# design.net
KiCad netlist of a schematic drawn in Altium Designer
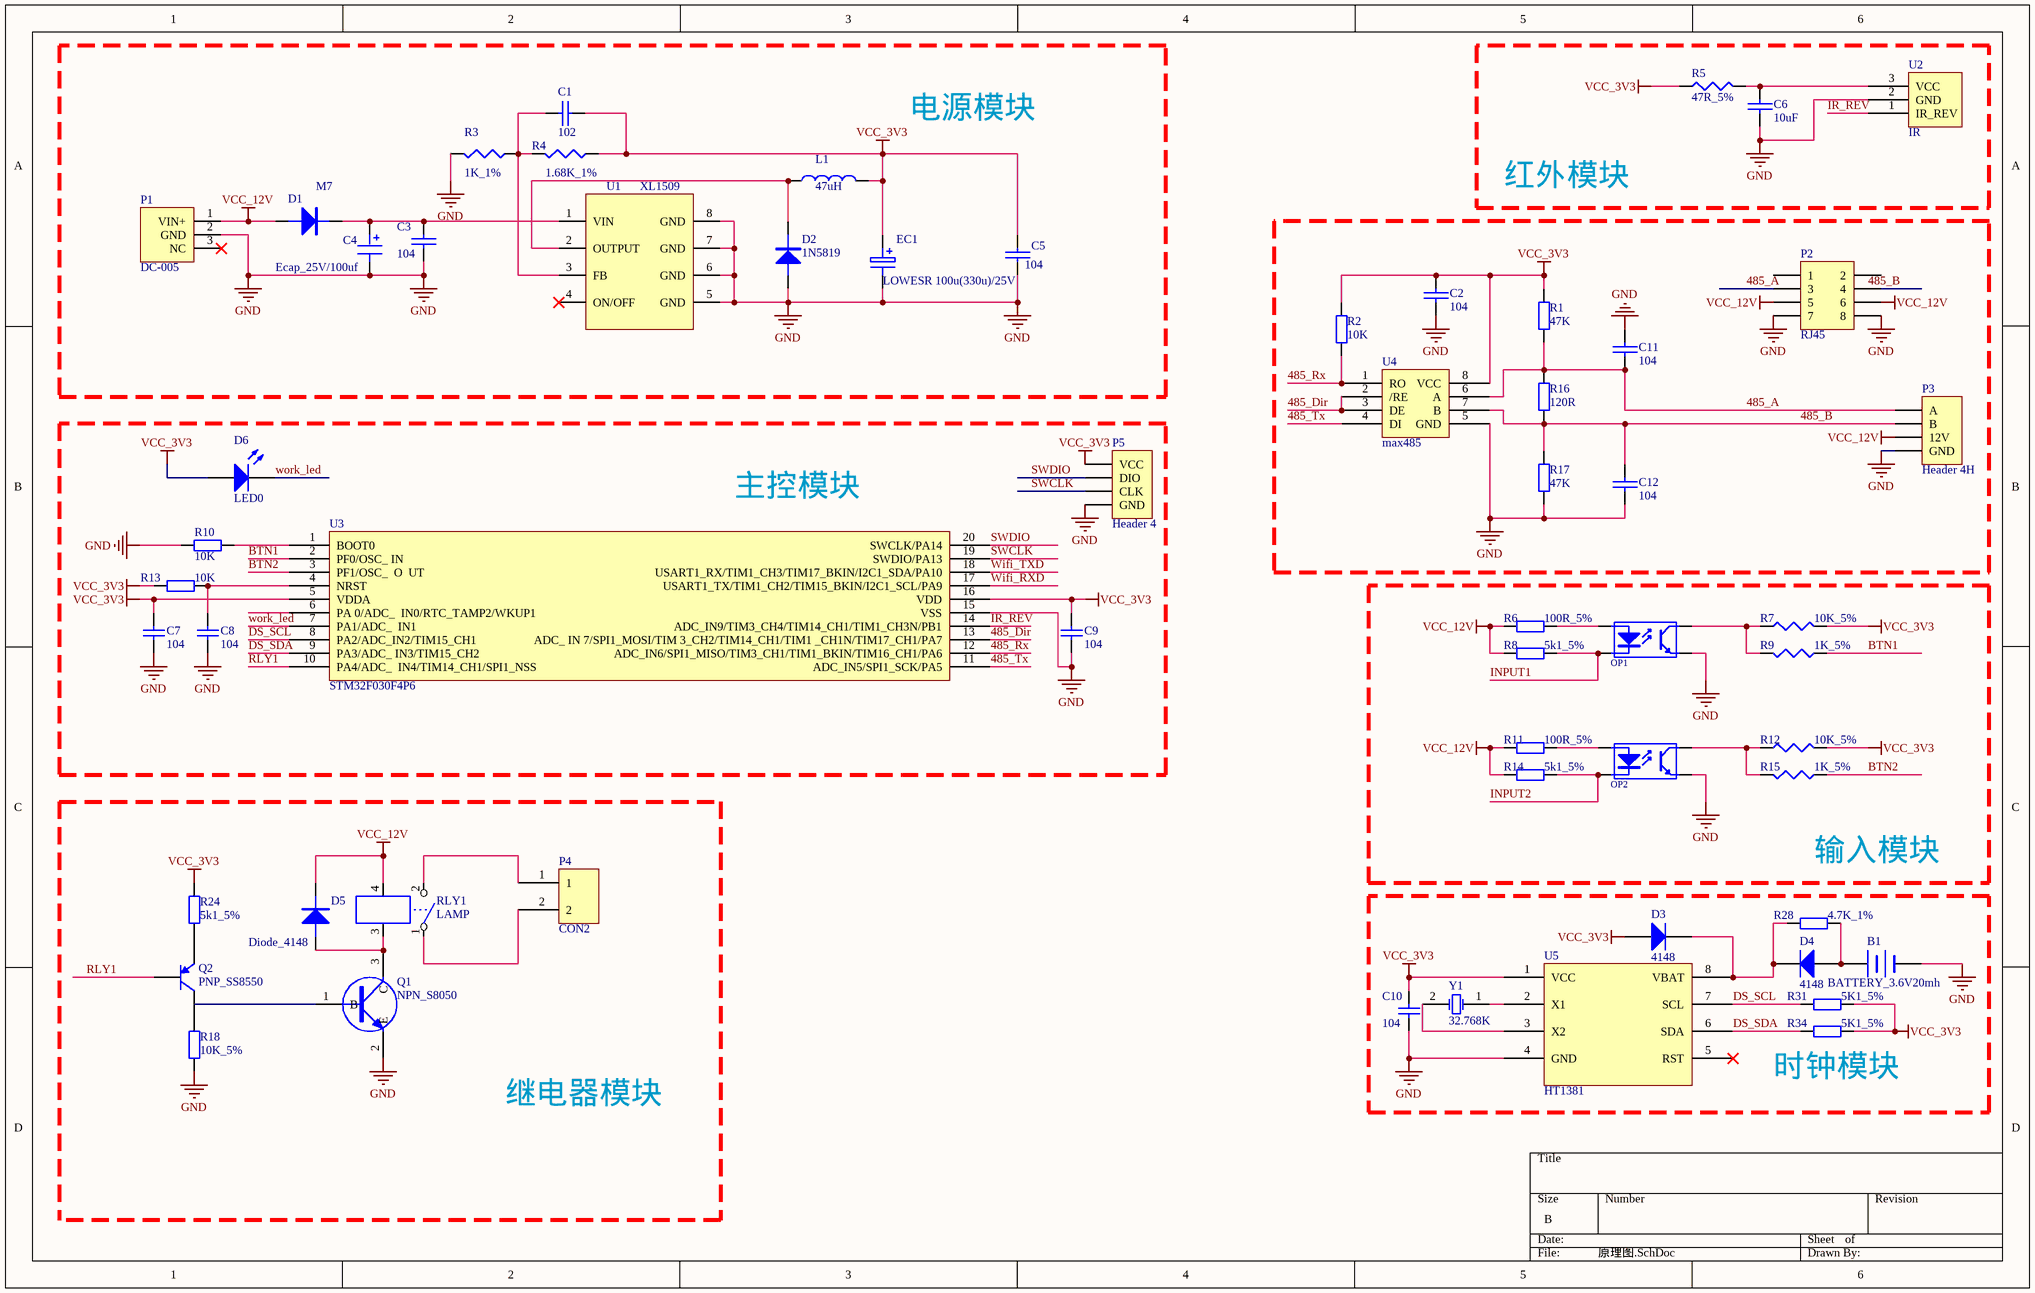
[diagram p0: 原理图.SchDoc]

(export (version "E")
  (design (tool "Eeschema 10.0.6"))
  (components
    (comp (ref "B1")
      (value "BATTERY_3.6V20mh")
      (footprint "NI-MH_20mA+C")
      (description "https://item.taobao.com/item.htm?spm=a1z10.5-c.w4002-471439023.33.YIdXb6&id=524181772992")
      (libsource (lib "NortCele_SchLib") (part "BATTERY_3.6V20mh"))
    )
    (comp (ref "C1") (value "102") (footprint "0603_CAP_SMT") (libsource (lib "*") (part "CAP")))
    (comp (ref "C2") (value "104") (footprint "0603_CAP_SMT") (libsource (lib "*") (part "CAP")))
    (comp (ref "C3") (value "104") (footprint "0603_CAP_SMT") (libsource (lib "*") (part "CAP")))
    (comp (ref "C4")
      (value "Ecap_25V/100uf")
      (footprint "SMT_CAP6.3")
      (description "https://item.taobao.com/item.htm?spm=a1z10.5-c.w4002-11020631983.33.qoX6of&id=7423722992")
      (libsource (lib "NortCele_SchLib") (part "Ecap_25V/100uf"))
    )
    (comp (ref "C5") (value "104") (footprint "0603_CAP_SMT") (libsource (lib "*") (part "CAP")))
    (comp (ref "C6") (value "10uF") (footprint "0805_CAP") (libsource (lib "Ruibo") (part "CAP")))
    (comp (ref "C7")
      (value "104")
      (footprint "C0402")
      (description "Capacitor")
      (fields (field (name "PUBLISHER") "Altium Limited"))
      (libsource (lib "Miscellaneous Devices") (part "Cap"))
    )
    (comp (ref "C8")
      (value "104")
      (footprint "C0402")
      (description "Capacitor")
      (fields (field (name "PUBLISHER") "Altium Limited"))
      (libsource (lib "Miscellaneous Devices") (part "Cap"))
    )
    (comp (ref "C9")
      (value "104")
      (footprint "C0402")
      (description "Capacitor")
      (fields (field (name "PUBLISHER") "Altium Limited"))
      (libsource (lib "Miscellaneous Devices") (part "Cap"))
    )
    (comp (ref "C10")
      (value "104")
      (footprint "0603_C")
      (description "https://item.taobao.com/item.htm?spm=a1z09.2.0.0.hNveX1&id=9716419590&_u=7ok62qs2673")
      (libsource (lib "NortCele_SchLib") (part "Cap_%10"))
    )
    (comp (ref "C11") (value "104") (footprint "0603_CAP_SMT") (libsource (lib "*") (part "CAP")))
    (comp (ref "C12") (value "104") (footprint "0603_CAP_SMT") (libsource (lib "*") (part "CAP")))
    (comp (ref "D1") (value "M7") (footprint "IN5819") (libsource (lib "*") (part "DIODE")))
    (comp (ref "D2") (value "1N5819") (footprint "SMD") (libsource (lib "Ruibo") (part "DIODE")))
    (comp (ref "D3")
      (value "4148")
      (footprint "SMAF_S5")
      (description "High Conductance Fast Diode")
      (fields (field (name "PUBLISHER") "Altium Limited"))
      (libsource (lib "Miscellaneous Devices") (part "Diode 1N914"))
    )
    (comp (ref "D4")
      (value "4148")
      (footprint "SMAF_S5")
      (description "High Conductance Fast Diode")
      (fields (field (name "PUBLISHER") "Altium Limited"))
      (libsource (lib "Miscellaneous Devices") (part "Diode 1N914"))
    )
    (comp (ref "D5")
      (value "Diode_4148")
      (footprint "SMD")
      (description "https://item.taobao.com/item.htm?spm=a1z10.3-c.w4002-11020657456.14.qD67rq&id=6126767310")
      (libsource (lib "NortCele_SchLib") (part "Diode_SS14"))
    )
    (comp (ref "D6")
      (value "LED0")
      (footprint "LED-0")
      (description "Typical INFRARED GaAs LED")
      (fields (field (name "PUBLISHER") "Altium Limited"))
      (libsource (lib "Miscellaneous Devices") (part "LED0"))
    )
    (comp (ref "EC1")
      (value "LOWESR 100u(330u)/25V")
      (footprint "SMT_CAP6.3")
      (libsource (lib "*") (part "ELECTRO1"))
    )
    (comp (ref "L1") (value "47uH") (footprint "0630") (libsource (lib "*") (part "INDUCTOR1")))
    (comp (ref "OP1")
      (value "EL817")
      (footprint "E817-SMD")
      (description "https://item.taobao.com/item.htm?spm=a1z10.3-c.w4002-11020657456.9.xiQJya&id=9840822052")
      (libsource (lib "NortCele_SchLib") (part "EL817"))
    )
    (comp (ref "OP2")
      (value "EL817")
      (footprint "E817-SMD")
      (description "https://item.taobao.com/item.htm?spm=a1z10.3-c.w4002-11020657456.9.xiQJya&id=9840822052")
      (libsource (lib "NortCele_SchLib") (part "EL817"))
    )
    (comp (ref "P1")
      (value "DC-005")
      (footprint "DC-5.5-2.1mm")
      (description "https://item.taobao.com/item.htm?spm=a1z10.3-c.w4002-11020657456.12.3OzBHB&id=5709638982")
      (libsource (lib "NortCele_SchLib") (part "DC-005"))
    )
    (comp (ref "P2")
      (value "RJ45")
      (footprint "HDR2X4")
      (description "Header, 4-Pin, Dual row")
      (fields (field (name "PUBLISHER") "Altium Limited"))
      (libsource (lib "Miscellaneous Connectors") (part "Header 4X2"))
    )
    (comp (ref "P3")
      (value "Header 4H")
      (footprint "HDR1X4H")
      (description "Header, 4-Pin, Right Angle")
      (fields (field (name "PUBLISHER") "Altium Limited"))
      (libsource (lib "Miscellaneous Connectors") (part "Header 4H"))
    )
    (comp (ref "P4") (value "CON2") (footprint "HP2PA-5.08") (libsource (lib "door") (part "CON2")))
    (comp (ref "P5")
      (value "Header 4")
      (footprint "HDR1X4")
      (description "Header, 4-Pin")
      (fields (field (name "PUBLISHER") "Altium Limited"))
      (libsource (lib "Miscellaneous Connectors") (part "Header 4"))
    )
    (comp (ref "Q1")
      (value "NPN_S8050")
      (footprint "SOT-23_FR")
      (description "https://item.taobao.com/item.htm?spm=a1z10.3-c.w4002-11020657456.15.ysrU5Y&id=5957247576")
      (libsource (lib "NortCele_SchLib") (part "NPN_S8050"))
    )
    (comp (ref "Q2")
      (value "PNP_SS8550")
      (footprint "TO-92A")
      (description "PNP General Purpose Amplifier")
      (fields (field (name "PUBLISHER") "Altium Limited"))
      (libsource (lib "Miscellaneous Devices") (part "2N3906"))
    )
    (comp (ref "R1")
      (value "47K")
      (footprint "0603_RES_SMT")
      (description "https://item.taobao.com/item.htm?spm=a1z10.3-c.w4002-11020657456.13.233szV&id=14686636311")
      (libsource (lib "NortCele_SchLib") (part "Res_%5"))
    )
    (comp (ref "R2")
      (value "10K")
      (footprint "0603_RES_SMT")
      (description "https://item.taobao.com/item.htm?spm=a1z10.3-c.w4002-11020657456.13.233szV&id=14686636311")
      (libsource (lib "NortCele_SchLib") (part "Res_%5"))
    )
    (comp (ref "R3") (value "1K_1%") (footprint "0603_RES_SMT") (libsource (lib "Ruibo") (part "RES")))
    (comp (ref "R4") (value "1.68K_1%") (footprint "0603_RES_SMT") (libsource (lib "Ruibo") (part "RES")))
    (comp (ref "R5") (value "47R_5%") (footprint "0805_RES") (libsource (lib "Ruibo") (part "RES")))
    (comp (ref "R6")
      (value "100R_5%")
      (footprint "0805_Res")
      (description "https://item.taobao.com/item.htm?spm=a1z10.3-c.w4002-11020657456.13.233szV&id=14686636311")
      (libsource (lib "NortCele_SchLib") (part "Res_5%"))
    )
    (comp (ref "R7") (value "10K_5%") (footprint "0805_RES") (libsource (lib "Ruibo") (part "RES")))
    (comp (ref "R8")
      (value "5k1_5%")
      (footprint "0805_Res")
      (description "https://item.taobao.com/item.htm?spm=a1z10.3-c.w4002-11020657456.13.233szV&id=14686636311")
      (libsource (lib "NortCele_SchLib") (part "Res_5%"))
    )
    (comp (ref "R9") (value "1K_5%") (footprint "0805_RES") (libsource (lib "Ruibo") (part "RES")))
    (comp (ref "R10")
      (value "10K")
      (footprint "R0402")
      (description "Resistor")
      (fields (field (name "PUBLISHER") "Altium Limited"))
      (libsource (lib "Miscellaneous Devices") (part "Res2"))
    )
    (comp (ref "R11")
      (value "100R_5%")
      (footprint "0805_Res")
      (description "https://item.taobao.com/item.htm?spm=a1z10.3-c.w4002-11020657456.13.233szV&id=14686636311")
      (libsource (lib "NortCele_SchLib") (part "Res_5%"))
    )
    (comp (ref "R12") (value "10K_5%") (footprint "0805_RES") (libsource (lib "Ruibo") (part "RES")))
    (comp (ref "R13")
      (value "10K")
      (footprint "R0402")
      (description "Resistor")
      (fields (field (name "PUBLISHER") "Altium Limited"))
      (libsource (lib "Miscellaneous Devices") (part "Res2"))
    )
    (comp (ref "R14")
      (value "5k1_5%")
      (footprint "0805_Res")
      (description "https://item.taobao.com/item.htm?spm=a1z10.3-c.w4002-11020657456.13.233szV&id=14686636311")
      (libsource (lib "NortCele_SchLib") (part "Res_5%"))
    )
    (comp (ref "R15") (value "1K_5%") (footprint "0805_RES") (libsource (lib "Ruibo") (part "RES")))
    (comp (ref "R16")
      (value "120R")
      (footprint "0603_RES_SMT")
      (description "https://item.taobao.com/item.htm?spm=a1z10.3-c.w4002-11020657456.13.233szV&id=14686636311")
      (libsource (lib "NortCele_SchLib") (part "Res_%5"))
    )
    (comp (ref "R17")
      (value "47K")
      (footprint "0603_RES_SMT")
      (description "https://item.taobao.com/item.htm?spm=a1z10.3-c.w4002-11020657456.13.233szV&id=14686636311")
      (libsource (lib "NortCele_SchLib") (part "Res_%5"))
    )
    (comp (ref "R18")
      (value "10K_5%")
      (footprint "R0402")
      (description "Resistor")
      (fields (field (name "PUBLISHER") "Altium Limited"))
      (libsource (lib "") (part "Res2_1"))
    )
    (comp (ref "R24")
      (value "5k1_5%")
      (footprint "R0402")
      (description "Resistor")
      (fields (field (name "PUBLISHER") "Altium Limited"))
      (libsource (lib "") (part "Res2_1"))
    )
    (comp (ref "R28")
      (value "4.7K_1%")
      (footprint "0603_R")
      (description "https://item.taobao.com/item.htm?spm=a1z10.3-c.w4002-11020657456.13.233szV&id=14686636311")
      (libsource (lib "NortCele_SchLib") (part "Res_5%"))
    )
    (comp (ref "R31")
      (value "5K1_5%")
      (footprint "0603_R")
      (description "https://item.taobao.com/item.htm?spm=a1z10.3-c.w4002-11020657456.13.233szV&id=14686636311")
      (libsource (lib "NortCele_SchLib") (part "Res_5%"))
    )
    (comp (ref "R34")
      (value "5K1_5%")
      (footprint "0603_R")
      (description "https://item.taobao.com/item.htm?spm=a1z10.3-c.w4002-11020657456.13.233szV&id=14686636311")
      (libsource (lib "") (part "Res_5%_1"))
    )
    (comp (ref "RLY1") (value "LAMP") (footprint "SANYOU_RLY112DM") (libsource (lib "*") (part "RELAY-SPST")))
    (comp (ref "U1") (value "XL1509") (footprint "SOP8") (libsource (lib "*") (part "XL1509")))
    (comp (ref "U2")
      (value "IR")
      (footprint "IR_REV_W3")
      (description "红外接收管")
      (libsource (lib "Ruibo") (part "IR_REV"))
    )
    (comp (ref "U3") (value "STM32F030F4P6") (libsource (lib "Schlib1") (part "STM32F030F4P6")))
    (comp (ref "U4") (value "max485") (footprint "SOP8") (libsource (lib "door") (part "max485")))
    (comp (ref "U5") (value "HT1381") (footprint "SOP-8_150mil") (libsource (lib "Schlib1") (part "DS1302")))
    (comp (ref "Y1")
      (value "32.768K")
      (footprint "SMD-3215_2P FC - 135")
      (description "Crystal Oscillator")
      (libsource (lib "Miscellaneous Devices") (part "XTAL"))
    )
  )
  (nets
    (net (code "1") (name "/485_A") (class "Default")
      (node (ref "C11") (pin "1") (pintype "passive"))
      (node (ref "P2") (pin "3") (pinfunction "3_3") (pintype "passive"))
      (node (ref "P3") (pin "1") (pinfunction "A_1") (pintype "passive"))
      (node (ref "R1") (pin "1") (pinfunction "1_1") (pintype "passive"))
      (node (ref "R16") (pin "2") (pinfunction "2_2") (pintype "passive"))
      (node (ref "U4") (pin "6") (pinfunction "A_6") (pintype "passive"))
    )
    (net (code "2") (name "/485_B") (class "Default")
      (node (ref "C12") (pin "2") (pintype "passive"))
      (node (ref "P3") (pin "2") (pinfunction "B_2") (pintype "passive"))
      (node (ref "R16") (pin "1") (pinfunction "1_1") (pintype "passive"))
      (node (ref "R17") (pin "2") (pinfunction "2_2") (pintype "passive"))
      (node (ref "U4") (pin "7") (pinfunction "B_7") (pintype "passive"))
    )
    (net (code "3") (name "/485_Dir") (class "Default")
      (node (ref "U3") (pin "13") (pinfunction "ADC__IN_7/SPI1_MOSI/TIM_3_CH2/TIM14_CH1/TIM1__CH1N/TIM17_CH1/PA7_13") (pintype "passive"))
      (node (ref "U4") (pin "2") (pinfunction "/RE_2") (pintype "passive"))
      (node (ref "U4") (pin "3") (pinfunction "DE_3") (pintype "passive"))
    )
    (net (code "4") (name "/485_Rx") (class "Default")
      (node (ref "R2") (pin "1") (pinfunction "1_1") (pintype "passive"))
      (node (ref "U3") (pin "12") (pinfunction "ADC_IN6/SPI1_MISO/TIM3_CH1/TIM1_BKIN/TIM16_CH1/PA6_12") (pintype "passive"))
      (node (ref "U4") (pin "1") (pinfunction "RO_1") (pintype "passive"))
    )
    (net (code "5") (name "/485_Tx") (class "Default")
      (node (ref "U3") (pin "11") (pinfunction "ADC_IN5/SPI1_SCK/PA5_11") (pintype "passive"))
      (node (ref "U4") (pin "4") (pinfunction "DI_4") (pintype "passive"))
    )
    (net (code "6") (name "/BTN1") (class "Default")
      (node (ref "R9") (pin "1") (pintype "passive"))
      (node (ref "U3") (pin "2") (pinfunction "PF0/OSC__IN_2") (pintype "passive"))
    )
    (net (code "7") (name "/BTN2") (class "Default")
      (node (ref "R15") (pin "1") (pintype "passive"))
      (node (ref "U3") (pin "3") (pinfunction "PF1/OSC___O__UT_3") (pintype "passive"))
    )
    (net (code "8") (name "/DS_SCL") (class "Default")
      (node (ref "R31") (pin "2") (pinfunction "2_2") (pintype "passive"))
      (node (ref "U3") (pin "8") (pinfunction "PA2/ADC_IN2/TIM15_CH1_8") (pintype "passive"))
      (node (ref "U5") (pin "7") (pinfunction "SCL_7") (pintype "passive"))
    )
    (net (code "9") (name "/DS_SDA") (class "Default")
      (node (ref "R34") (pin "1") (pinfunction "1_1") (pintype "passive"))
      (node (ref "U3") (pin "9") (pinfunction "PA3/ADC__IN3/TIM15_CH2_9") (pintype "passive"))
      (node (ref "U5") (pin "6") (pinfunction "SDA_6") (pintype "passive"))
    )
    (net (code "10") (name "/INPUT1") (class "Default")
      (node (ref "OP1") (pin "2") (pinfunction "K_2") (pintype "passive"))
      (node (ref "R8") (pin "1") (pinfunction "1_1") (pintype "passive"))
    )
    (net (code "11") (name "/INPUT2") (class "Default")
      (node (ref "OP2") (pin "2") (pinfunction "K_2") (pintype "passive"))
      (node (ref "R14") (pin "1") (pinfunction "1_1") (pintype "passive"))
    )
    (net (code "12") (name "/IR_REV") (class "Default")
      (node (ref "U2") (pin "1") (pinfunction "IR_REV_1") (pintype "passive"))
      (node (ref "U3") (pin "14") (pinfunction "ADC_IN9/TIM3_CH4/TIM14_CH1/TIM1_CH3N/PB1_14") (pintype "passive"))
    )
    (net (code "13") (name "/RLY1") (class "Default")
      (node (ref "Q2") (pin "2") (pinfunction "B_2") (pintype "passive"))
      (node (ref "U3") (pin "10") (pinfunction "PA4/ADC___IN4/TIM14_CH1/SPI1_NSS_10") (pintype "passive"))
    )
    (net (code "14") (name "/SWCLK") (class "Default")
      (node (ref "P5") (pin "3") (pinfunction "CLK_3") (pintype "passive"))
      (node (ref "U3") (pin "19") (pinfunction "SWDIO/PA13_19") (pintype "passive"))
    )
    (net (code "15") (name "/SWDIO") (class "Default")
      (node (ref "P5") (pin "2") (pinfunction "DIO_2") (pintype "passive"))
      (node (ref "U3") (pin "20") (pinfunction "SWCLK/PA14_20") (pintype "passive"))
    )
    (net (code "16") (name "/Wifi_RXD") (class "Default")
      (node (ref "U3") (pin "17") (pinfunction "USART1_TX/TIM1_CH2/TIM15_BKIN/I2C1_SCL/PA9_17") (pintype "passive"))
    )
    (net (code "17") (name "/Wifi_TXD") (class "Default")
      (node (ref "U3") (pin "18") (pinfunction "USART1_RX/TIM1_CH3/TIM17_BKIN/I2C1_SDA/PA10_18") (pintype "passive"))
    )
    (net (code "18") (name "/work_led") (class "Default")
      (node (ref "D6") (pin "2") (pinfunction "K_2") (pintype "passive"))
      (node (ref "U3") (pin "7") (pinfunction "PA1/ADC___IN1_7") (pintype "passive"))
    )
    (net (code "19") (name "GND") (class "Default")
      (node (ref "B1") (pin "2") (pinfunction "-_2") (pintype "passive"))
      (node (ref "C10") (pin "1") (pinfunction "1_1") (pintype "passive"))
      (node (ref "C11") (pin "2") (pintype "passive"))
      (node (ref "C12") (pin "1") (pintype "passive"))
      (node (ref "C2") (pin "1") (pintype "passive"))
      (node (ref "C3") (pin "2") (pintype "passive"))
      (node (ref "C4") (pin "2") (pinfunction "2_2") (pintype "passive"))
      (node (ref "C5") (pin "2") (pintype "passive"))
      (node (ref "C6") (pin "2") (pintype "passive"))
      (node (ref "C7") (pin "1") (pinfunction "1_1") (pintype "passive"))
      (node (ref "C8") (pin "1") (pinfunction "1_1") (pintype "passive"))
      (node (ref "C9") (pin "1") (pinfunction "1_1") (pintype "passive"))
      (node (ref "D2") (pin "A") (pintype "passive"))
      (node (ref "EC1") (pin "2") (pintype "passive"))
      (node (ref "OP1") (pin "3") (pinfunction "E_3") (pintype "passive"))
      (node (ref "OP2") (pin "3") (pinfunction "E_3") (pintype "passive"))
      (node (ref "P1") (pin "2") (pinfunction "GND_2") (pintype "passive"))
      (node (ref "P2") (pin "7") (pinfunction "7_7") (pintype "passive"))
      (node (ref "P2") (pin "8") (pinfunction "8_8") (pintype "passive"))
      (node (ref "P3") (pin "4") (pinfunction "GND_4") (pintype "passive"))
      (node (ref "P5") (pin "4") (pinfunction "GND_4") (pintype "passive"))
      (node (ref "Q1") (pin "2") (pinfunction "E_2") (pintype "passive"))
      (node (ref "R10") (pin "1") (pinfunction "1_1") (pintype "passive"))
      (node (ref "R17") (pin "1") (pinfunction "1_1") (pintype "passive"))
      (node (ref "R18") (pin "1") (pinfunction "1_1") (pintype "passive"))
      (node (ref "R3") (pin "2") (pintype "passive"))
      (node (ref "U1") (pin "5") (pinfunction "GND_5") (pintype "passive"))
      (node (ref "U1") (pin "6") (pinfunction "GND_6") (pintype "passive"))
      (node (ref "U1") (pin "7") (pinfunction "GND_7") (pintype "passive"))
      (node (ref "U1") (pin "8") (pinfunction "GND_8") (pintype "passive"))
      (node (ref "U2") (pin "2") (pinfunction "GND_2") (pintype "passive"))
      (node (ref "U3") (pin "15") (pinfunction "VSS_15") (pintype "passive"))
      (node (ref "U4") (pin "5") (pinfunction "GND_5") (pintype "passive"))
      (node (ref "U5") (pin "4") (pinfunction "GND_4") (pintype "passive"))
    )
    (net (code "20") (name "Net-(B1-+)") (class "Default")
      (node (ref "B1") (pin "1") (pinfunction "+_1") (pintype "passive"))
      (node (ref "D4") (pin "1") (pinfunction "A_1") (pintype "passive"))
      (node (ref "R28") (pin "1") (pinfunction "1_1") (pintype "passive"))
    )
    (net (code "21") (name "Net-(D1-2)") (class "Default")
      (node (ref "C3") (pin "1") (pintype "passive"))
      (node (ref "C4") (pin "1") (pinfunction "1_1") (pintype "passive"))
      (node (ref "D1") (pin "K") (pinfunction "2_K") (pintype "passive"))
      (node (ref "U1") (pin "1") (pinfunction "VIN_1") (pintype "passive"))
    )
    (net (code "22") (name "Net-(D3-K)") (class "Default")
      (node (ref "D3") (pin "2") (pinfunction "K_2") (pintype "passive"))
      (node (ref "D4") (pin "2") (pinfunction "K_2") (pintype "passive"))
      (node (ref "R28") (pin "2") (pinfunction "2_2") (pintype "passive"))
      (node (ref "U5") (pin "8") (pinfunction "VBAT_8") (pintype "passive"))
    )
    (net (code "23") (name "Net-(D5-1)") (class "Default")
      (node (ref "D5") (pin "A") (pinfunction "1_A") (pintype "passive"))
      (node (ref "Q1") (pin "3") (pinfunction "C_3") (pintype "passive"))
      (node (ref "RLY1") (pin "3") (pintype "passive"))
    )
    (net (code "24") (name "Net-(OP1-A)") (class "Default")
      (node (ref "OP1") (pin "1") (pinfunction "A_1") (pintype "passive"))
      (node (ref "R6") (pin "1") (pinfunction "1_1") (pintype "passive"))
    )
    (net (code "25") (name "Net-(OP1-C)") (class "Default")
      (node (ref "OP1") (pin "4") (pinfunction "C_4") (pintype "passive"))
      (node (ref "R7") (pin "1") (pintype "passive"))
      (node (ref "R9") (pin "2") (pintype "passive"))
    )
    (net (code "26") (name "Net-(OP2-A)") (class "Default")
      (node (ref "OP2") (pin "1") (pinfunction "A_1") (pintype "passive"))
      (node (ref "R11") (pin "1") (pinfunction "1_1") (pintype "passive"))
    )
    (net (code "27") (name "Net-(OP2-C)") (class "Default")
      (node (ref "OP2") (pin "4") (pinfunction "C_4") (pintype "passive"))
      (node (ref "R12") (pin "1") (pintype "passive"))
      (node (ref "R15") (pin "2") (pintype "passive"))
    )
    (net (code "28") (name "Net-(P4-Pad1)") (class "Default")
      (node (ref "P4") (pin "1") (pinfunction "1_1") (pintype "passive"))
      (node (ref "RLY1") (pin "2") (pintype "passive"))
    )
    (net (code "29") (name "Net-(P4-Pad2)") (class "Default")
      (node (ref "P4") (pin "2") (pinfunction "2_2") (pintype "passive"))
      (node (ref "RLY1") (pin "1") (pintype "passive"))
    )
    (net (code "30") (name "Net-(Q2-C)") (class "Default")
      (node (ref "Q2") (pin "3") (pinfunction "C_3") (pintype "passive"))
      (node (ref "R18") (pin "2") (pinfunction "2_2") (pintype "passive"))
    )
    (net (code "31") (name "Net-(Q2-E)") (class "Default")
      (node (ref "Q2") (pin "1") (pinfunction "E_1") (pintype "passive"))
      (node (ref "R24") (pin "1") (pinfunction "1_1") (pintype "passive"))
    )
    (net (code "32") (name "Net-(U1-FB)") (class "Default")
      (node (ref "C1") (pin "1") (pintype "passive"))
      (node (ref "R3") (pin "1") (pintype "passive"))
      (node (ref "R4") (pin "2") (pintype "passive"))
      (node (ref "U1") (pin "3") (pinfunction "FB_3") (pintype "passive"))
    )
    (net (code "33") (name "Net-(U1-OUTPUT)") (class "Default")
      (node (ref "D2") (pin "K") (pintype "passive"))
      (node (ref "L1") (pin "1") (pinfunction "1_1") (pintype "passive"))
      (node (ref "U1") (pin "2") (pinfunction "OUTPUT_2") (pintype "passive"))
    )
    (net (code "34") (name "Net-(U2-VCC)") (class "Default")
      (node (ref "C6") (pin "1") (pintype "passive"))
      (node (ref "R5") (pin "2") (pintype "passive"))
      (node (ref "U2") (pin "3") (pinfunction "VCC_3") (pintype "passive"))
    )
    (net (code "35") (name "Net-(U3-BOOT0)") (class "Default")
      (node (ref "R10") (pin "2") (pinfunction "2_2") (pintype "passive"))
      (node (ref "U3") (pin "1") (pinfunction "BOOT0_1") (pintype "passive"))
    )
    (net (code "36") (name "Net-(U3-NRST)") (class "Default")
      (node (ref "C8") (pin "2") (pinfunction "2_2") (pintype "passive"))
      (node (ref "R13") (pin "2") (pinfunction "2_2") (pintype "passive"))
      (node (ref "U3") (pin "4") (pinfunction "NRST_4") (pintype "passive"))
    )
    (net (code "37") (name "Net-(U5-X1)") (class "Default")
      (node (ref "U5") (pin "2") (pinfunction "X1_2") (pintype "passive"))
      (node (ref "Y1") (pin "1") (pinfunction "OSC1_1") (pintype "passive"))
    )
    (net (code "38") (name "Net-(U5-X2)") (class "Default")
      (node (ref "U5") (pin "3") (pinfunction "X2_3") (pintype "passive"))
      (node (ref "Y1") (pin "2") (pinfunction "OSC2_2") (pintype "passive"))
    )
    (net (code "39") (name "VCC_3V3") (class "Default")
      (node (ref "C1") (pin "2") (pintype "passive"))
      (node (ref "C10") (pin "2") (pinfunction "2_2") (pintype "passive"))
      (node (ref "C2") (pin "2") (pintype "passive"))
      (node (ref "C5") (pin "1") (pintype "passive"))
      (node (ref "C7") (pin "2") (pinfunction "2_2") (pintype "passive"))
      (node (ref "C9") (pin "2") (pinfunction "2_2") (pintype "passive"))
      (node (ref "D3") (pin "1") (pinfunction "A_1") (pintype "passive"))
      (node (ref "D6") (pin "1") (pinfunction "A_1") (pintype "passive"))
      (node (ref "EC1") (pin "1") (pintype "passive"))
      (node (ref "L1") (pin "2") (pinfunction "2_2") (pintype "passive"))
      (node (ref "P5") (pin "1") (pinfunction "VCC_1") (pintype "passive"))
      (node (ref "R1") (pin "2") (pinfunction "2_2") (pintype "passive"))
      (node (ref "R12") (pin "2") (pintype "passive"))
      (node (ref "R13") (pin "1") (pinfunction "1_1") (pintype "passive"))
      (node (ref "R2") (pin "2") (pinfunction "2_2") (pintype "passive"))
      (node (ref "R24") (pin "2") (pinfunction "2_2") (pintype "passive"))
      (node (ref "R31") (pin "1") (pinfunction "1_1") (pintype "passive"))
      (node (ref "R34") (pin "2") (pinfunction "2_2") (pintype "passive"))
      (node (ref "R4") (pin "1") (pintype "passive"))
      (node (ref "R5") (pin "1") (pintype "passive"))
      (node (ref "R7") (pin "2") (pintype "passive"))
      (node (ref "U3") (pin "16") (pinfunction "VDD_16") (pintype "passive"))
      (node (ref "U3") (pin "5") (pinfunction "VDDA_5") (pintype "passive"))
      (node (ref "U4") (pin "8") (pinfunction "VCC_8") (pintype "passive"))
      (node (ref "U5") (pin "1") (pinfunction "VCC_1") (pintype "passive"))
    )
    (net (code "40") (name "VCC_12V") (class "Default")
      (node (ref "D1") (pin "A") (pinfunction "1_A") (pintype "passive"))
      (node (ref "D5") (pin "K") (pinfunction "2_K") (pintype "passive"))
      (node (ref "P1") (pin "1") (pinfunction "VIN+_1") (pintype "passive"))
      (node (ref "P2") (pin "5") (pinfunction "5_5") (pintype "passive"))
      (node (ref "P2") (pin "6") (pinfunction "6_6") (pintype "passive"))
      (node (ref "P3") (pin "3") (pinfunction "12V_3") (pintype "passive"))
      (node (ref "R11") (pin "2") (pinfunction "2_2") (pintype "passive"))
      (node (ref "R14") (pin "2") (pinfunction "2_2") (pintype "passive"))
      (node (ref "R6") (pin "2") (pinfunction "2_2") (pintype "passive"))
      (node (ref "R8") (pin "2") (pinfunction "2_2") (pintype "passive"))
      (node (ref "RLY1") (pin "4") (pintype "passive"))
    )
    (net (code "41") (name "unconnected-(P1-NC-Pad3)") (class "Default")
      (node (ref "P1") (pin "3") (pinfunction "NC_3") (pintype "passive+no_connect"))
    )
    (net (code "42") (name "unconnected-(P2-Pad1)") (class "Default")
      (node (ref "P2") (pin "1") (pinfunction "1_1") (pintype "passive"))
    )
    (net (code "43") (name "unconnected-(P2-Pad2)") (class "Default")
      (node (ref "P2") (pin "2") (pinfunction "2_2") (pintype "passive"))
    )
    (net (code "44") (name "unconnected-(P2-Pad4)") (class "Default")
      (node (ref "P2") (pin "4") (pinfunction "4_4") (pintype "passive"))
    )
    (net (code "45") (name "unconnected-(Q1-B-Pad1)") (class "Default")
      (node (ref "Q1") (pin "1") (pinfunction "B_1") (pintype "passive"))
    )
    (net (code "46") (name "unconnected-(U1-ON{slash}OFF-Pad4)") (class "Default")
      (node (ref "U1") (pin "4") (pinfunction "ON/OFF_4") (pintype "passive+no_connect"))
    )
    (net (code "47") (name "unconnected-(U3-PA_0{slash}ADC___IN0{slash}RTC_TAMP2{slash}WKUP1-Pad6)") (class "Default")
      (node (ref "U3") (pin "6") (pinfunction "PA_0/ADC___IN0/RTC_TAMP2/WKUP1_6") (pintype "passive"))
    )
    (net (code "48") (name "unconnected-(U5-RST-Pad5)") (class "Default")
      (node (ref "U5") (pin "5") (pinfunction "RST_5") (pintype "passive+no_connect"))
    )
  )
)
